# ESP32.net
KiCad netlist of a schematic drawn in Altium Designer
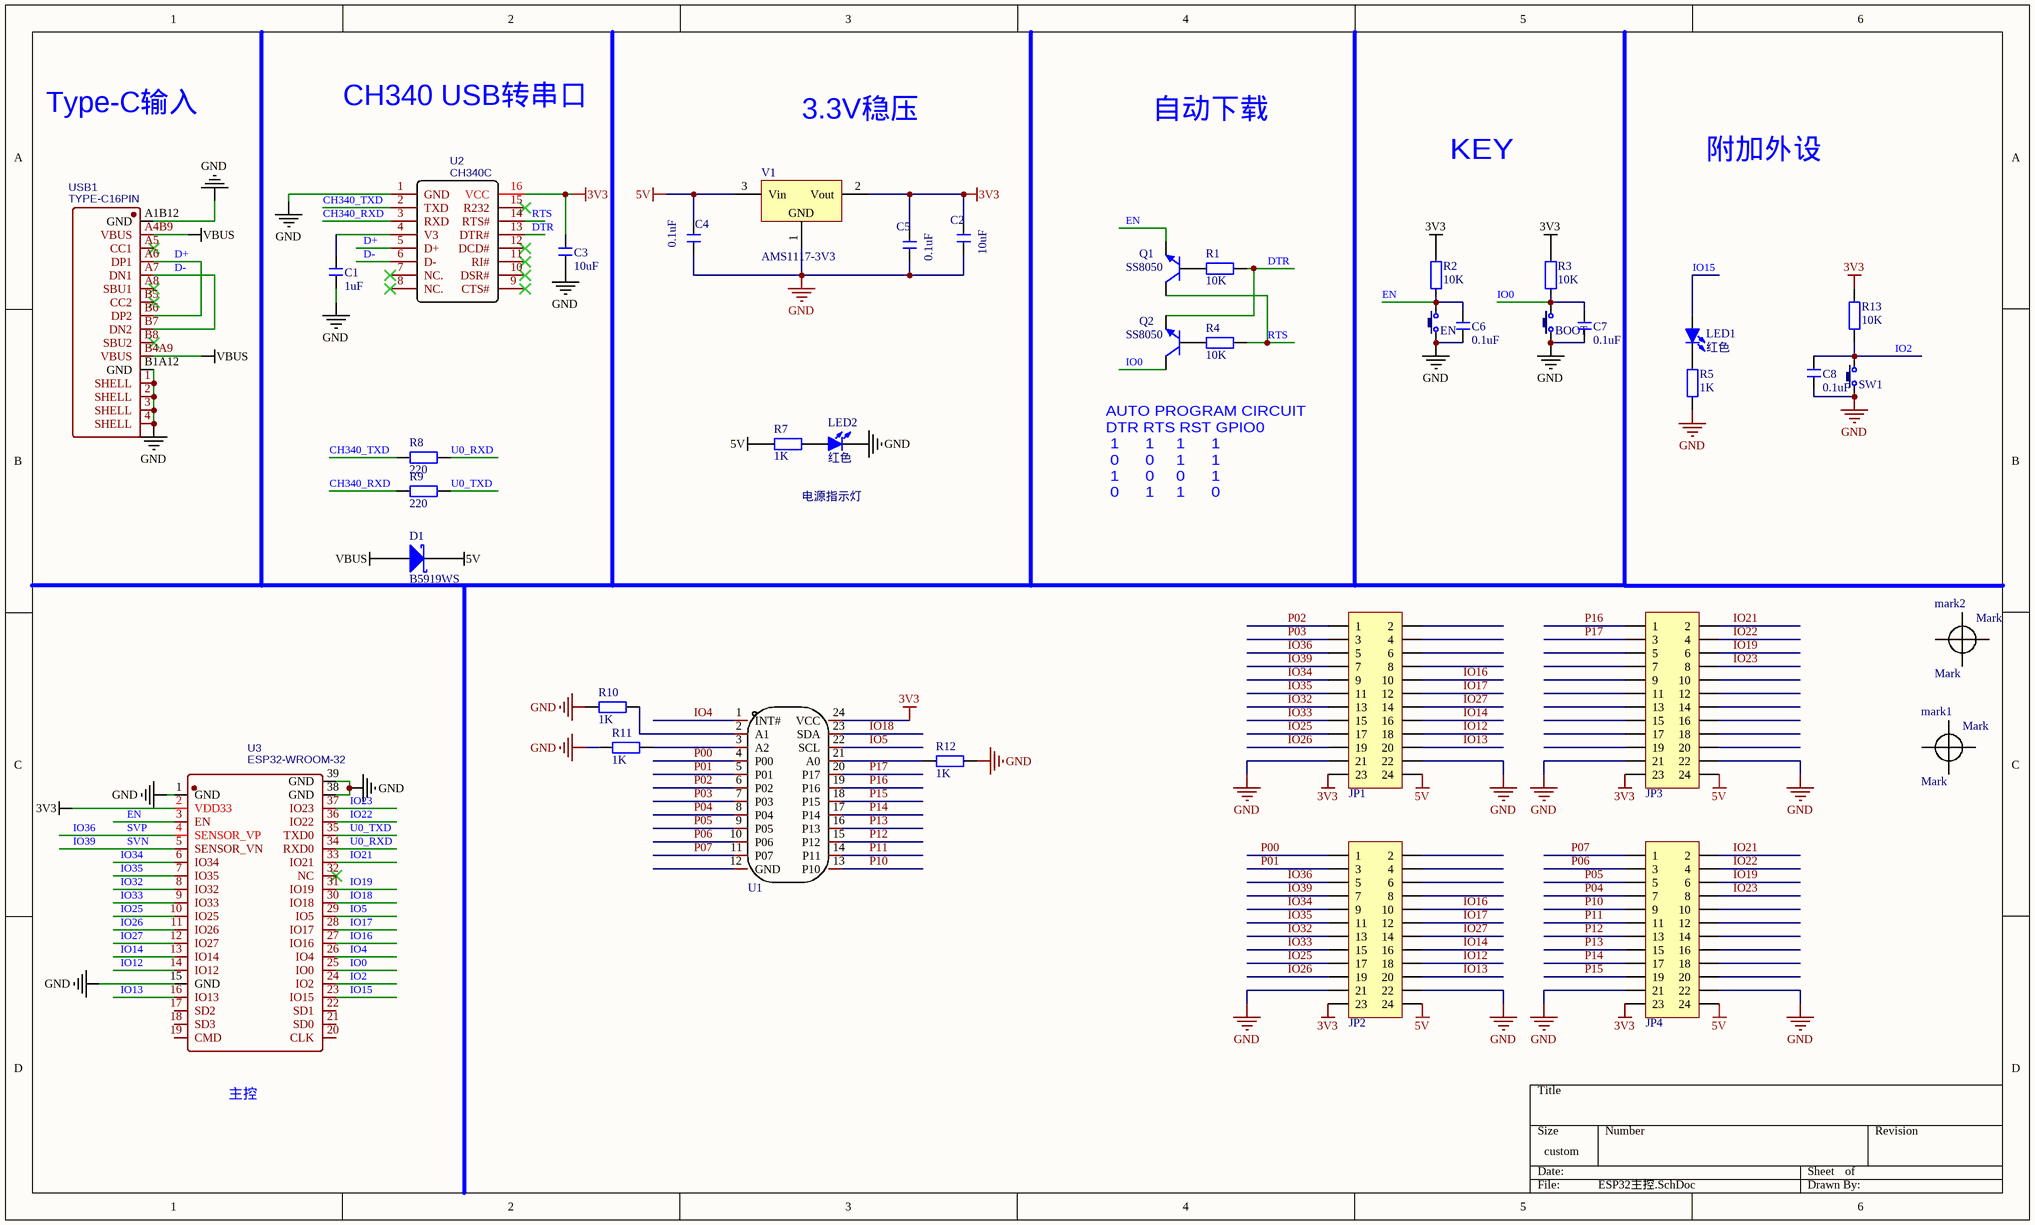
[diagram p0: ESP32主控.SchDoc]

(export (version "E")
  (design (tool "Eeschema 10.0.6"))
  (components
    (comp (ref "BOOT")
      (value "3x6x5")
      (footprint "TSW SMD-3*6*2.5")
      (description "3x6轻触开关")
      (fields (field (name "版权归属") "封装库来自淘宝 ID：黄晶宝石"))
      (libsource (lib "0.7 - 常用按键-开关") (part "TSW 3x6"))
    )
    (comp (ref "C1")
      (value "1uF")
      (footprint "C 0603_L")
      (description "贴片电容")
      (libsource (lib "0.1 - 电阻-电容-电感") (part "C"))
    )
    (comp (ref "C2")
      (value "10uF")
      (footprint "C 0603_M")
      (description "贴片电容")
      (libsource (lib "0.1 - 电阻-电容-电感") (part "C"))
    )
    (comp (ref "C3")
      (value "10uF")
      (footprint "C 0603_L")
      (description "贴片电容")
      (libsource (lib "0.1 - 电阻-电容-电感") (part "C"))
    )
    (comp (ref "C4")
      (value "0.1uF")
      (footprint "C 0603_M")
      (description "贴片电容")
      (libsource (lib "0.1 - 电阻-电容-电感") (part "C"))
    )
    (comp (ref "C5")
      (value "0.1uF")
      (footprint "C 0603_M")
      (description "贴片电容")
      (libsource (lib "0.1 - 电阻-电容-电感") (part "C"))
    )
    (comp (ref "C6")
      (value "0.1uF")
      (footprint "C 0603_L")
      (description "贴片电容")
      (libsource (lib "0.1 - 电阻-电容-电感") (part "C"))
    )
    (comp (ref "C7")
      (value "0.1uF")
      (footprint "C 0603_L")
      (description "贴片电容")
      (libsource (lib "0.1 - 电阻-电容-电感") (part "C"))
    )
    (comp (ref "C8")
      (value "0.1uF")
      (footprint "C 0603_L")
      (description "贴片电容")
      (libsource (lib "0.1 - 电阻-电容-电感") (part "C"))
    )
    (comp (ref "D1")
      (value "B5919WS")
      (footprint "SOD-323")
      (description "肖特基二极管")
      (libsource (lib "0.2 - 二极管-整流桥") (part "1N5819"))
    )
    (comp (ref "EN")
      (value "3x6x5")
      (footprint "TSW SMD-3*6*2.5")
      (description "3x6轻触开关")
      (fields (field (name "版权归属") "封装库来自淘宝 ID：黄晶宝石"))
      (libsource (lib "0.7 - 常用按键-开关") (part "TSW 3x6"))
    )
    (comp (ref "JP1")
      (value "Header 2X11")
      (footprint "HDR2.54-WI-2x12P")
      (description "12*2P接插件")
      (fields (field (name "版权归属") "封装库来自淘宝卖家 ID：黄晶宝石"))
      (libsource (lib "5.4 - 接插件-脚距2.54 (100mil) ") (part "Header 12X2"))
    )
    (comp (ref "JP2")
      (value "Header 2X11")
      (footprint "HDR2.54-WI-2x12P")
      (description "12*2P接插件")
      (fields (field (name "版权归属") "封装库来自淘宝卖家 ID：黄晶宝石"))
      (libsource (lib "5.4 - 接插件-脚距2.54 (100mil) ") (part "Header 12X2"))
    )
    (comp (ref "JP3")
      (value "Header 2X11")
      (footprint "HDR2.54-WI-2x12P")
      (description "12*2P接插件")
      (fields (field (name "版权归属") "封装库来自淘宝卖家 ID：黄晶宝石"))
      (libsource (lib "5.4 - 接插件-脚距2.54 (100mil) ") (part "Header 12X2"))
    )
    (comp (ref "JP4")
      (value "Header 2X11")
      (footprint "HDR2.54-WI-2x12P")
      (description "12*2P接插件")
      (fields (field (name "版权归属") "封装库来自淘宝卖家 ID：黄晶宝石"))
      (libsource (lib "5.4 - 接插件-脚距2.54 (100mil) ") (part "Header 12X2"))
    )
    (comp (ref "LED1")
      (value "红色")
      (footprint "LED 0603R")
      (description "贴片LED")
      (fields (field (name "版权归属") "封装库来自淘宝 ID：黄晶宝石"))
      (libsource (lib "0.3 - LED发光二极管") (part "LED-SMD"))
    )
    (comp (ref "LED2")
      (value "红色")
      (footprint "LED 0603R")
      (description "贴片LED")
      (fields (field (name "版权归属") "封装库来自淘宝 ID：黄晶宝石"))
      (libsource (lib "0.3 - LED发光二极管") (part "LED-SMD"))
    )
    (comp (ref "mark1") (value "Mark") (footprint "Mark:Mark") (libsource (lib "Mark") (part "Mark")))
    (comp (ref "mark2") (value "Mark") (footprint "Mark:Mark") (libsource (lib "Mark") (part "Mark")))
    (comp (ref "Q1")
      (value "SS8050")
      (footprint "SOT23-3N")
      (description "高频放大-NPN型")
      (fields (field (name "版权归属") "封装库来自淘宝 ID：黄晶宝石"))
      (libsource (lib "0.4 - 三极管") (part "8050-SMD"))
    )
    (comp (ref "Q2")
      (value "SS8050")
      (footprint "SOT23-3N")
      (description "高频放大-NPN型")
      (fields (field (name "版权归属") "封装库来自淘宝 ID：黄晶宝石"))
      (libsource (lib "0.4 - 三极管") (part "8050-SMD"))
    )
    (comp (ref "R1")
      (value "10K")
      (footprint "R 0603_L")
      (description "贴片电阻")
      (fields (field (name "版权归属") "来自淘宝 ID：黄晶宝石"))
      (libsource (lib "0.1 - 电阻-电容-电感") (part "R"))
    )
    (comp (ref "R2")
      (value "10K")
      (footprint "R 0603_L")
      (description "贴片电阻")
      (fields (field (name "版权归属") "来自淘宝 ID：黄晶宝石"))
      (libsource (lib "0.1 - 电阻-电容-电感") (part "R"))
    )
    (comp (ref "R3")
      (value "10K")
      (footprint "R 0603_L")
      (description "贴片电阻")
      (fields (field (name "版权归属") "来自淘宝 ID：黄晶宝石"))
      (libsource (lib "0.1 - 电阻-电容-电感") (part "R"))
    )
    (comp (ref "R4")
      (value "10K")
      (footprint "R 0603_L")
      (description "贴片电阻")
      (fields (field (name "版权归属") "来自淘宝 ID：黄晶宝石"))
      (libsource (lib "0.1 - 电阻-电容-电感") (part "R"))
    )
    (comp (ref "R5")
      (value "1K")
      (footprint "R 0603_L")
      (description "贴片电阻")
      (fields (field (name "版权归属") "来自淘宝 ID：黄晶宝石"))
      (libsource (lib "0.1 - 电阻-电容-电感") (part "R"))
    )
    (comp (ref "R7")
      (value "1K")
      (footprint "R 0603_L")
      (description "贴片电阻")
      (fields (field (name "版权归属") "来自淘宝 ID：黄晶宝石"))
      (libsource (lib "0.1 - 电阻-电容-电感") (part "R"))
    )
    (comp (ref "R8")
      (value "220")
      (footprint "R 0603_L")
      (description "贴片电阻")
      (fields (field (name "版权归属") "来自淘宝 ID：黄晶宝石"))
      (libsource (lib "0.1 - 电阻-电容-电感") (part "R"))
    )
    (comp (ref "R9")
      (value "220")
      (footprint "R 0603_L")
      (description "贴片电阻")
      (fields (field (name "版权归属") "来自淘宝 ID：黄晶宝石"))
      (libsource (lib "0.1 - 电阻-电容-电感") (part "R"))
    )
    (comp (ref "R10")
      (value "1K")
      (footprint "R 0603_L")
      (description "贴片电阻")
      (fields (field (name "版权归属") "来自淘宝 ID：黄晶宝石"))
      (libsource (lib "0.1 - 电阻-电容-电感") (part "R"))
    )
    (comp (ref "R11")
      (value "1K")
      (footprint "R 0603_L")
      (description "贴片电阻")
      (fields (field (name "版权归属") "来自淘宝 ID：黄晶宝石"))
      (libsource (lib "0.1 - 电阻-电容-电感") (part "R"))
    )
    (comp (ref "R12")
      (value "1K")
      (footprint "R 0603_L")
      (description "贴片电阻")
      (fields (field (name "版权归属") "来自淘宝 ID：黄晶宝石"))
      (libsource (lib "0.1 - 电阻-电容-电感") (part "R"))
    )
    (comp (ref "R13")
      (value "10K")
      (footprint "R 0603_L")
      (description "贴片电阻")
      (fields (field (name "版权归属") "来自淘宝 ID：黄晶宝石"))
      (libsource (lib "0.1 - 电阻-电容-电感") (part "R"))
    )
    (comp (ref "SW1")
      (value "3x6x5")
      (footprint "TSW SMD-3*6*2.5")
      (description "3x6轻触开关")
      (fields (field (name "版权归属") "封装库来自淘宝 ID：黄晶宝石"))
      (libsource (lib "0.7 - 常用按键-开关") (part "TSW 3x6"))
    )
    (comp (ref "U1")
      (value "PCA9555DW")
      (footprint "PCA9555DW")
      (description "具有中断、弱上拉和配置寄存器的 16 位 2.3V 至 5.5V I2C/SMBus I/O 扩展器 24-SOIC -40 to 85")
      (fields (field (name "MANUFACTURER") "TI(德州仪器)"))
      (libsource (lib "PCA9555DW") (part "PCA9555DW"))
    )
    (comp (ref "U2")
      (value "CH340C")
      (footprint "SOP-16_L10.0-W3.9-P1.27-LS6.0-BL")
      (fields (field (name "BOM_SUPPLIER PART") "C84681"))
      (libsource (lib "altium-import") (part "root_0_CH340C_"))
    )
    (comp (ref "U3")
      (value "ESP32-WROOM-32")
      (footprint "WIFIM-SMD_39P-L25.5-W18.0-P1.27")
      (fields (field (name "BOM_SUPPLIER PART") "C503587") (field (name "CONTRIBUTOR") "LCSC"))
      (libsource (lib "altium-import") (part "root_0_ESP32-WROOM-32_"))
    )
    (comp (ref "USB1")
      (value "TYPE-C16PIN")
      (footprint "USB-C-SMD_TYPE-C16PIN")
      (fields (field (name "BOM_SUPPLIER PART") "C393939") (field (name "CONTRIBUTOR") "LCSC"))
      (libsource (lib "altium-import") (part "root_0_TYPE-C16PIN_"))
    )
    (comp (ref "V1")
      (value "AMS1117-3V3")
      (footprint "SOT223_L")
      (description "三端稳压芯片")
      (libsource (lib "1.1 - 电源类芯片") (part "AMS1117"))
    )
  )
  (nets
    (net (code "1") (name "/CH340_RXD") (class "Default")
      (node (ref "R9") (pin "1") (pinfunction "1_1") (pintype "passive"))
      (node (ref "U2") (pin "3") (pinfunction "RXD_3") (pintype "passive"))
    )
    (net (code "2") (name "/CH340_TXD") (class "Default")
      (node (ref "R8") (pin "1") (pinfunction "1_1") (pintype "passive"))
      (node (ref "U2") (pin "2") (pinfunction "TXD_2") (pintype "passive"))
    )
    (net (code "3") (name "/D+") (class "Default")
      (node (ref "U2") (pin "5") (pinfunction "D+_5") (pintype "passive"))
      (node (ref "USB1") (pin "A6") (pinfunction "DP1_A6") (pintype "passive"))
      (node (ref "USB1") (pin "B6") (pinfunction "DP2_B6") (pintype "passive"))
    )
    (net (code "4") (name "/D-") (class "Default")
      (node (ref "U2") (pin "6") (pinfunction "D-_6") (pintype "passive"))
      (node (ref "USB1") (pin "A7") (pinfunction "DN1_A7") (pintype "passive"))
      (node (ref "USB1") (pin "B7") (pinfunction "DN2_B7") (pintype "passive"))
    )
    (net (code "5") (name "/DTR") (class "Default")
      (node (ref "Q2") (pin "2") (pinfunction "E_2") (pintype "passive"))
      (node (ref "R1") (pin "2") (pinfunction "2_2") (pintype "passive"))
      (node (ref "U2") (pin "13") (pinfunction "DTR#_13") (pintype "passive"))
    )
    (net (code "6") (name "/EN") (class "Default")
      (node (ref "C6") (pin "2") (pinfunction "2_2") (pintype "passive"))
      (node (ref "EN") (pin "2") (pinfunction "2_2") (pintype "passive"))
      (node (ref "Q1") (pin "2") (pinfunction "E_2") (pintype "passive"))
      (node (ref "R2") (pin "1") (pinfunction "1_1") (pintype "passive"))
      (node (ref "U3") (pin "3") (pinfunction "EN_3") (pintype "passive"))
    )
    (net (code "7") (name "/IO0") (class "Default")
      (node (ref "BOOT") (pin "2") (pinfunction "2_2") (pintype "passive"))
      (node (ref "C7") (pin "2") (pinfunction "2_2") (pintype "passive"))
      (node (ref "Q2") (pin "3") (pinfunction "C_3") (pintype "passive"))
      (node (ref "R3") (pin "1") (pinfunction "1_1") (pintype "passive"))
      (node (ref "U3") (pin "25") (pinfunction "IO0_25") (pintype "passive"))
    )
    (net (code "8") (name "/IO2") (class "Default")
      (node (ref "C8") (pin "2") (pinfunction "2_2") (pintype "passive"))
      (node (ref "R13") (pin "1") (pinfunction "1_1") (pintype "passive"))
      (node (ref "SW1") (pin "2") (pinfunction "2_2") (pintype "passive"))
      (node (ref "U3") (pin "24") (pinfunction "IO2_24") (pintype "passive"))
    )
    (net (code "9") (name "/IO4") (class "Default")
      (node (ref "U1") (pin "1") (pinfunction "INT#_1") (pintype "passive"))
      (node (ref "U3") (pin "26") (pinfunction "IO4_26") (pintype "passive"))
    )
    (net (code "10") (name "/IO5") (class "Default")
      (node (ref "U1") (pin "22") (pinfunction "SCL_22") (pintype "passive"))
      (node (ref "U3") (pin "29") (pinfunction "IO5_29") (pintype "passive"))
    )
    (net (code "11") (name "/IO12") (class "Default")
      (node (ref "JP1") (pin "18") (pinfunction "18_18") (pintype "passive"))
      (node (ref "JP2") (pin "18") (pinfunction "18_18") (pintype "passive"))
      (node (ref "U3") (pin "14") (pinfunction "IO12_14") (pintype "passive"))
    )
    (net (code "12") (name "/IO13") (class "Default")
      (node (ref "JP1") (pin "20") (pinfunction "20_20") (pintype "passive"))
      (node (ref "JP2") (pin "20") (pinfunction "20_20") (pintype "passive"))
      (node (ref "U3") (pin "16") (pinfunction "IO13_16") (pintype "passive"))
    )
    (net (code "13") (name "/IO14") (class "Default")
      (node (ref "JP1") (pin "16") (pinfunction "16_16") (pintype "passive"))
      (node (ref "JP2") (pin "16") (pinfunction "16_16") (pintype "passive"))
      (node (ref "U3") (pin "13") (pinfunction "IO14_13") (pintype "passive"))
    )
    (net (code "14") (name "/IO15") (class "Default")
      (node (ref "LED1") (pin "1") (pinfunction "A_1") (pintype "passive"))
      (node (ref "U3") (pin "23") (pinfunction "IO15_23") (pintype "passive"))
    )
    (net (code "15") (name "/IO16") (class "Default")
      (node (ref "JP1") (pin "10") (pinfunction "10_10") (pintype "passive"))
      (node (ref "JP2") (pin "10") (pinfunction "10_10") (pintype "passive"))
      (node (ref "U3") (pin "27") (pinfunction "IO16_27") (pintype "passive"))
    )
    (net (code "16") (name "/IO17") (class "Default")
      (node (ref "JP1") (pin "12") (pinfunction "12_12") (pintype "passive"))
      (node (ref "JP2") (pin "12") (pinfunction "12_12") (pintype "passive"))
      (node (ref "U3") (pin "28") (pinfunction "IO17_28") (pintype "passive"))
    )
    (net (code "17") (name "/IO18") (class "Default")
      (node (ref "U1") (pin "23") (pinfunction "SDA_23") (pintype "passive"))
      (node (ref "U3") (pin "30") (pinfunction "IO18_30") (pintype "passive"))
    )
    (net (code "18") (name "/IO19") (class "Default")
      (node (ref "JP3") (pin "6") (pinfunction "6_6") (pintype "passive"))
      (node (ref "JP4") (pin "6") (pinfunction "6_6") (pintype "passive"))
      (node (ref "U3") (pin "31") (pinfunction "IO19_31") (pintype "passive"))
    )
    (net (code "19") (name "/IO21") (class "Default")
      (node (ref "JP3") (pin "2") (pinfunction "2_2") (pintype "passive"))
      (node (ref "JP4") (pin "2") (pinfunction "2_2") (pintype "passive"))
      (node (ref "U3") (pin "33") (pinfunction "IO21_33") (pintype "passive"))
    )
    (net (code "20") (name "/IO22") (class "Default")
      (node (ref "JP3") (pin "4") (pinfunction "4_4") (pintype "passive"))
      (node (ref "JP4") (pin "4") (pinfunction "4_4") (pintype "passive"))
      (node (ref "U3") (pin "36") (pinfunction "IO22_36") (pintype "passive"))
    )
    (net (code "21") (name "/IO23") (class "Default")
      (node (ref "JP3") (pin "8") (pinfunction "8_8") (pintype "passive"))
      (node (ref "JP4") (pin "8") (pinfunction "8_8") (pintype "passive"))
      (node (ref "U3") (pin "37") (pinfunction "IO23_37") (pintype "passive"))
    )
    (net (code "22") (name "/IO25") (class "Default")
      (node (ref "JP1") (pin "17") (pinfunction "17_17") (pintype "passive"))
      (node (ref "JP2") (pin "17") (pinfunction "17_17") (pintype "passive"))
      (node (ref "U3") (pin "10") (pinfunction "IO25_10") (pintype "passive"))
    )
    (net (code "23") (name "/IO26") (class "Default")
      (node (ref "JP1") (pin "19") (pinfunction "19_19") (pintype "passive"))
      (node (ref "JP2") (pin "19") (pinfunction "19_19") (pintype "passive"))
      (node (ref "U3") (pin "11") (pinfunction "IO26_11") (pintype "passive"))
    )
    (net (code "24") (name "/IO27") (class "Default")
      (node (ref "JP1") (pin "14") (pinfunction "14_14") (pintype "passive"))
      (node (ref "JP2") (pin "14") (pinfunction "14_14") (pintype "passive"))
      (node (ref "U3") (pin "12") (pinfunction "IO27_12") (pintype "passive"))
    )
    (net (code "25") (name "/IO32") (class "Default")
      (node (ref "JP1") (pin "13") (pinfunction "13_13") (pintype "passive"))
      (node (ref "JP2") (pin "13") (pinfunction "13_13") (pintype "passive"))
      (node (ref "U3") (pin "8") (pinfunction "IO32_8") (pintype "passive"))
    )
    (net (code "26") (name "/IO33") (class "Default")
      (node (ref "JP1") (pin "15") (pinfunction "15_15") (pintype "passive"))
      (node (ref "JP2") (pin "15") (pinfunction "15_15") (pintype "passive"))
      (node (ref "U3") (pin "9") (pinfunction "IO33_9") (pintype "passive"))
    )
    (net (code "27") (name "/IO34") (class "Default")
      (node (ref "JP1") (pin "9") (pinfunction "9_9") (pintype "passive"))
      (node (ref "JP2") (pin "9") (pinfunction "9_9") (pintype "passive"))
      (node (ref "U3") (pin "6") (pinfunction "IO34_6") (pintype "passive"))
    )
    (net (code "28") (name "/IO35") (class "Default")
      (node (ref "JP1") (pin "11") (pinfunction "11_11") (pintype "passive"))
      (node (ref "JP2") (pin "11") (pinfunction "11_11") (pintype "passive"))
      (node (ref "U3") (pin "7") (pinfunction "IO35_7") (pintype "passive"))
    )
    (net (code "29") (name "/IO36") (class "Default")
      (node (ref "JP1") (pin "5") (pinfunction "5_5") (pintype "passive"))
      (node (ref "JP2") (pin "5") (pinfunction "5_5") (pintype "passive"))
      (node (ref "U3") (pin "4") (pinfunction "SENSOR_VP_4") (pintype "passive"))
    )
    (net (code "30") (name "/IO39") (class "Default")
      (node (ref "JP1") (pin "7") (pinfunction "7_7") (pintype "passive"))
      (node (ref "JP2") (pin "7") (pinfunction "7_7") (pintype "passive"))
      (node (ref "U3") (pin "5") (pinfunction "SENSOR_VN_5") (pintype "passive"))
    )
    (net (code "31") (name "/P00") (class "Default")
      (node (ref "JP2") (pin "1") (pinfunction "1_1") (pintype "passive"))
      (node (ref "U1") (pin "4") (pinfunction "P00_4") (pintype "passive"))
    )
    (net (code "32") (name "/P01") (class "Default")
      (node (ref "JP2") (pin "3") (pinfunction "3_3") (pintype "passive"))
      (node (ref "U1") (pin "5") (pinfunction "P01_5") (pintype "passive"))
    )
    (net (code "33") (name "/P02") (class "Default")
      (node (ref "JP1") (pin "1") (pinfunction "1_1") (pintype "passive"))
      (node (ref "U1") (pin "6") (pinfunction "P02_6") (pintype "passive"))
    )
    (net (code "34") (name "/P03") (class "Default")
      (node (ref "JP1") (pin "3") (pinfunction "3_3") (pintype "passive"))
      (node (ref "U1") (pin "7") (pinfunction "P03_7") (pintype "passive"))
    )
    (net (code "35") (name "/P04") (class "Default")
      (node (ref "JP4") (pin "7") (pinfunction "7_7") (pintype "passive"))
      (node (ref "U1") (pin "8") (pinfunction "P04_8") (pintype "passive"))
    )
    (net (code "36") (name "/P05") (class "Default")
      (node (ref "JP4") (pin "5") (pinfunction "5_5") (pintype "passive"))
      (node (ref "U1") (pin "9") (pinfunction "P05_9") (pintype "passive"))
    )
    (net (code "37") (name "/P06") (class "Default")
      (node (ref "JP4") (pin "3") (pinfunction "3_3") (pintype "passive"))
      (node (ref "U1") (pin "10") (pinfunction "P06_10") (pintype "passive"))
    )
    (net (code "38") (name "/P07") (class "Default")
      (node (ref "JP4") (pin "1") (pinfunction "1_1") (pintype "passive"))
      (node (ref "U1") (pin "11") (pinfunction "P07_11") (pintype "passive"))
    )
    (net (code "39") (name "/P10") (class "Default")
      (node (ref "JP4") (pin "9") (pinfunction "9_9") (pintype "passive"))
      (node (ref "U1") (pin "13") (pinfunction "P10_13") (pintype "passive"))
    )
    (net (code "40") (name "/P11") (class "Default")
      (node (ref "JP4") (pin "11") (pinfunction "11_11") (pintype "passive"))
      (node (ref "U1") (pin "14") (pinfunction "P11_14") (pintype "passive"))
    )
    (net (code "41") (name "/P12") (class "Default")
      (node (ref "JP4") (pin "13") (pinfunction "13_13") (pintype "passive"))
      (node (ref "U1") (pin "15") (pinfunction "P12_15") (pintype "passive"))
    )
    (net (code "42") (name "/P13") (class "Default")
      (node (ref "JP4") (pin "15") (pinfunction "15_15") (pintype "passive"))
      (node (ref "U1") (pin "16") (pinfunction "P13_16") (pintype "passive"))
    )
    (net (code "43") (name "/P14") (class "Default")
      (node (ref "JP4") (pin "17") (pinfunction "17_17") (pintype "passive"))
      (node (ref "U1") (pin "17") (pinfunction "P14_17") (pintype "passive"))
    )
    (net (code "44") (name "/P15") (class "Default")
      (node (ref "JP4") (pin "19") (pinfunction "19_19") (pintype "passive"))
      (node (ref "U1") (pin "18") (pinfunction "P15_18") (pintype "passive"))
    )
    (net (code "45") (name "/P16") (class "Default")
      (node (ref "JP3") (pin "1") (pinfunction "1_1") (pintype "passive"))
      (node (ref "U1") (pin "19") (pinfunction "P16_19") (pintype "passive"))
    )
    (net (code "46") (name "/P17") (class "Default")
      (node (ref "JP3") (pin "3") (pinfunction "3_3") (pintype "passive"))
      (node (ref "U1") (pin "20") (pinfunction "P17_20") (pintype "passive"))
    )
    (net (code "47") (name "/RTS") (class "Default")
      (node (ref "Q1") (pin "3") (pinfunction "C_3") (pintype "passive"))
      (node (ref "R4") (pin "2") (pinfunction "2_2") (pintype "passive"))
      (node (ref "U2") (pin "14") (pinfunction "RTS#_14") (pintype "passive"))
    )
    (net (code "48") (name "/U0_RXD") (class "Default")
      (node (ref "R8") (pin "2") (pinfunction "2_2") (pintype "passive"))
      (node (ref "U3") (pin "34") (pinfunction "RXD0_34") (pintype "passive"))
    )
    (net (code "49") (name "/U0_TXD") (class "Default")
      (node (ref "R9") (pin "2") (pinfunction "2_2") (pintype "passive"))
      (node (ref "U3") (pin "35") (pinfunction "TXD0_35") (pintype "passive"))
    )
    (net (code "50") (name "3V3") (class "Default")
      (node (ref "C2") (pin "2") (pinfunction "2_2") (pintype "passive"))
      (node (ref "C3") (pin "2") (pinfunction "2_2") (pintype "passive"))
      (node (ref "C5") (pin "2") (pinfunction "2_2") (pintype "passive"))
      (node (ref "JP1") (pin "23") (pinfunction "23_23") (pintype "passive"))
      (node (ref "JP2") (pin "23") (pinfunction "23_23") (pintype "passive"))
      (node (ref "JP3") (pin "23") (pinfunction "23_23") (pintype "passive"))
      (node (ref "JP4") (pin "23") (pinfunction "23_23") (pintype "passive"))
      (node (ref "R13") (pin "2") (pinfunction "2_2") (pintype "passive"))
      (node (ref "R2") (pin "2") (pinfunction "2_2") (pintype "passive"))
      (node (ref "R3") (pin "2") (pinfunction "2_2") (pintype "passive"))
      (node (ref "U1") (pin "24") (pinfunction "VCC_24") (pintype "passive"))
      (node (ref "U2") (pin "16") (pinfunction "VCC_16") (pintype "passive"))
      (node (ref "U3") (pin "2") (pinfunction "VDD33_2") (pintype "passive"))
      (node (ref "V1") (pin "2") (pinfunction "Vout_2") (pintype "passive"))
    )
    (net (code "51") (name "5V") (class "Default")
      (node (ref "C4") (pin "2") (pinfunction "2_2") (pintype "passive"))
      (node (ref "D1") (pin "2") (pinfunction "K_2") (pintype "passive"))
      (node (ref "JP1") (pin "24") (pinfunction "24_24") (pintype "passive"))
      (node (ref "JP2") (pin "24") (pinfunction "24_24") (pintype "passive"))
      (node (ref "JP3") (pin "24") (pinfunction "24_24") (pintype "passive"))
      (node (ref "JP4") (pin "24") (pinfunction "24_24") (pintype "passive"))
      (node (ref "R7") (pin "1") (pinfunction "1_1") (pintype "passive"))
      (node (ref "V1") (pin "3") (pinfunction "Vin_3") (pintype "passive"))
    )
    (net (code "52") (name "GND") (class "Default")
      (node (ref "BOOT") (pin "1") (pinfunction "1_1") (pintype "passive"))
      (node (ref "C1") (pin "1") (pinfunction "1_1") (pintype "passive"))
      (node (ref "C2") (pin "1") (pinfunction "1_1") (pintype "passive"))
      (node (ref "C3") (pin "1") (pinfunction "1_1") (pintype "passive"))
      (node (ref "C4") (pin "1") (pinfunction "1_1") (pintype "passive"))
      (node (ref "C5") (pin "1") (pinfunction "1_1") (pintype "passive"))
      (node (ref "C6") (pin "1") (pinfunction "1_1") (pintype "passive"))
      (node (ref "C7") (pin "1") (pinfunction "1_1") (pintype "passive"))
      (node (ref "C8") (pin "1") (pinfunction "1_1") (pintype "passive"))
      (node (ref "EN") (pin "1") (pinfunction "1_1") (pintype "passive"))
      (node (ref "JP1") (pin "21") (pinfunction "21_21") (pintype "passive"))
      (node (ref "JP1") (pin "22") (pinfunction "22_22") (pintype "passive"))
      (node (ref "JP2") (pin "21") (pinfunction "21_21") (pintype "passive"))
      (node (ref "JP2") (pin "22") (pinfunction "22_22") (pintype "passive"))
      (node (ref "JP3") (pin "21") (pinfunction "21_21") (pintype "passive"))
      (node (ref "JP3") (pin "22") (pinfunction "22_22") (pintype "passive"))
      (node (ref "JP4") (pin "21") (pinfunction "21_21") (pintype "passive"))
      (node (ref "JP4") (pin "22") (pinfunction "22_22") (pintype "passive"))
      (node (ref "LED2") (pin "2") (pinfunction "K_2") (pintype "passive"))
      (node (ref "R10") (pin "1") (pinfunction "1_1") (pintype "passive"))
      (node (ref "R11") (pin "1") (pinfunction "1_1") (pintype "passive"))
      (node (ref "R12") (pin "2") (pinfunction "2_2") (pintype "passive"))
      (node (ref "R5") (pin "1") (pinfunction "1_1") (pintype "passive"))
      (node (ref "SW1") (pin "1") (pinfunction "1_1") (pintype "passive"))
      (node (ref "U2") (pin "1") (pinfunction "GND_1") (pintype "passive"))
      (node (ref "U3") (pin "1") (pinfunction "GND_1") (pintype "passive"))
      (node (ref "U3") (pin "15") (pinfunction "GND_15") (pintype "passive"))
      (node (ref "U3") (pin "38") (pinfunction "GND_38") (pintype "passive"))
      (node (ref "U3") (pin "39") (pinfunction "GND_39") (pintype "passive"))
      (node (ref "USB1") (pin "1") (pinfunction "SHELL_1") (pintype "passive"))
      (node (ref "USB1") (pin "2") (pinfunction "SHELL_2") (pintype "passive"))
      (node (ref "USB1") (pin "3") (pinfunction "SHELL_3") (pintype "passive"))
      (node (ref "USB1") (pin "4") (pinfunction "SHELL_4") (pintype "passive"))
      (node (ref "USB1") (pin "A1B12") (pinfunction "GND_A1B12") (pintype "passive"))
      (node (ref "USB1") (pin "B1A12") (pinfunction "GND_B1A12") (pintype "passive"))
      (node (ref "V1") (pin "1") (pinfunction "GND_1") (pintype "passive"))
    )
    (net (code "53") (name "Net-(LED1-K)") (class "Default")
      (node (ref "LED1") (pin "2") (pinfunction "K_2") (pintype "passive"))
      (node (ref "R5") (pin "2") (pinfunction "2_2") (pintype "passive"))
    )
    (net (code "54") (name "Net-(LED2-A)") (class "Default")
      (node (ref "LED2") (pin "1") (pinfunction "A_1") (pintype "passive"))
      (node (ref "R7") (pin "2") (pinfunction "2_2") (pintype "passive"))
    )
    (net (code "55") (name "Net-(Q1-B)") (class "Default")
      (node (ref "Q1") (pin "1") (pinfunction "B_1") (pintype "passive"))
      (node (ref "R1") (pin "1") (pinfunction "1_1") (pintype "passive"))
    )
    (net (code "56") (name "Net-(Q2-B)") (class "Default")
      (node (ref "Q2") (pin "1") (pinfunction "B_1") (pintype "passive"))
      (node (ref "R4") (pin "1") (pinfunction "1_1") (pintype "passive"))
    )
    (net (code "57") (name "Net-(U1-A0)") (class "Default")
      (node (ref "R12") (pin "1") (pinfunction "1_1") (pintype "passive"))
      (node (ref "U1") (pin "21") (pinfunction "A0_21") (pintype "passive"))
    )
    (net (code "58") (name "Net-(U1-A1)") (class "Default")
      (node (ref "R10") (pin "2") (pinfunction "2_2") (pintype "passive"))
      (node (ref "U1") (pin "2") (pinfunction "A1_2") (pintype "passive"))
    )
    (net (code "59") (name "Net-(U1-A2)") (class "Default")
      (node (ref "R11") (pin "2") (pinfunction "2_2") (pintype "passive"))
      (node (ref "U1") (pin "3") (pinfunction "A2_3") (pintype "passive"))
    )
    (net (code "60") (name "Net-(U2-V3)") (class "Default")
      (node (ref "C1") (pin "2") (pinfunction "2_2") (pintype "passive"))
      (node (ref "U2") (pin "4") (pinfunction "V3_4") (pintype "passive"))
    )
    (net (code "61") (name "VBUS") (class "Default")
      (node (ref "D1") (pin "1") (pinfunction "A_1") (pintype "passive"))
      (node (ref "USB1") (pin "A4B9") (pinfunction "VBUS_A4B9") (pintype "passive"))
      (node (ref "USB1") (pin "B4A9") (pinfunction "VBUS_B4A9") (pintype "passive"))
    )
    (net (code "62") (name "unconnected-(JP1-Pad2)") (class "Default")
      (node (ref "JP1") (pin "2") (pinfunction "2_2") (pintype "passive"))
    )
    (net (code "63") (name "unconnected-(JP1-Pad4)") (class "Default")
      (node (ref "JP1") (pin "4") (pinfunction "4_4") (pintype "passive"))
    )
    (net (code "64") (name "unconnected-(JP1-Pad6)") (class "Default")
      (node (ref "JP1") (pin "6") (pinfunction "6_6") (pintype "passive"))
    )
    (net (code "65") (name "unconnected-(JP1-Pad8)") (class "Default")
      (node (ref "JP1") (pin "8") (pinfunction "8_8") (pintype "passive"))
    )
    (net (code "66") (name "unconnected-(JP2-Pad2)") (class "Default")
      (node (ref "JP2") (pin "2") (pinfunction "2_2") (pintype "passive"))
    )
    (net (code "67") (name "unconnected-(JP2-Pad4)") (class "Default")
      (node (ref "JP2") (pin "4") (pinfunction "4_4") (pintype "passive"))
    )
    (net (code "68") (name "unconnected-(JP2-Pad6)") (class "Default")
      (node (ref "JP2") (pin "6") (pinfunction "6_6") (pintype "passive"))
    )
    (net (code "69") (name "unconnected-(JP2-Pad8)") (class "Default")
      (node (ref "JP2") (pin "8") (pinfunction "8_8") (pintype "passive"))
    )
    (net (code "70") (name "unconnected-(JP3-Pad5)") (class "Default")
      (node (ref "JP3") (pin "5") (pinfunction "5_5") (pintype "passive"))
    )
    (net (code "71") (name "unconnected-(JP3-Pad7)") (class "Default")
      (node (ref "JP3") (pin "7") (pinfunction "7_7") (pintype "passive"))
    )
    (net (code "72") (name "unconnected-(JP3-Pad9)") (class "Default")
      (node (ref "JP3") (pin "9") (pinfunction "9_9") (pintype "passive"))
    )
    (net (code "73") (name "unconnected-(JP3-Pad10)") (class "Default")
      (node (ref "JP3") (pin "10") (pinfunction "10_10") (pintype "passive"))
    )
    (net (code "74") (name "unconnected-(JP3-Pad11)") (class "Default")
      (node (ref "JP3") (pin "11") (pinfunction "11_11") (pintype "passive"))
    )
    (net (code "75") (name "unconnected-(JP3-Pad12)") (class "Default")
      (node (ref "JP3") (pin "12") (pinfunction "12_12") (pintype "passive"))
    )
    (net (code "76") (name "unconnected-(JP3-Pad13)") (class "Default")
      (node (ref "JP3") (pin "13") (pinfunction "13_13") (pintype "passive"))
    )
    (net (code "77") (name "unconnected-(JP3-Pad14)") (class "Default")
      (node (ref "JP3") (pin "14") (pinfunction "14_14") (pintype "passive"))
    )
    (net (code "78") (name "unconnected-(JP3-Pad15)") (class "Default")
      (node (ref "JP3") (pin "15") (pinfunction "15_15") (pintype "passive"))
    )
    (net (code "79") (name "unconnected-(JP3-Pad16)") (class "Default")
      (node (ref "JP3") (pin "16") (pinfunction "16_16") (pintype "passive"))
    )
    (net (code "80") (name "unconnected-(JP3-Pad17)") (class "Default")
      (node (ref "JP3") (pin "17") (pinfunction "17_17") (pintype "passive"))
    )
    (net (code "81") (name "unconnected-(JP3-Pad18)") (class "Default")
      (node (ref "JP3") (pin "18") (pinfunction "18_18") (pintype "passive"))
    )
    (net (code "82") (name "unconnected-(JP3-Pad19)") (class "Default")
      (node (ref "JP3") (pin "19") (pinfunction "19_19") (pintype "passive"))
    )
    (net (code "83") (name "unconnected-(JP3-Pad20)") (class "Default")
      (node (ref "JP3") (pin "20") (pinfunction "20_20") (pintype "passive"))
    )
    (net (code "84") (name "unconnected-(JP4-Pad10)") (class "Default")
      (node (ref "JP4") (pin "10") (pinfunction "10_10") (pintype "passive"))
    )
    (net (code "85") (name "unconnected-(JP4-Pad12)") (class "Default")
      (node (ref "JP4") (pin "12") (pinfunction "12_12") (pintype "passive"))
    )
    (net (code "86") (name "unconnected-(JP4-Pad14)") (class "Default")
      (node (ref "JP4") (pin "14") (pinfunction "14_14") (pintype "passive"))
    )
    (net (code "87") (name "unconnected-(JP4-Pad16)") (class "Default")
      (node (ref "JP4") (pin "16") (pinfunction "16_16") (pintype "passive"))
    )
    (net (code "88") (name "unconnected-(JP4-Pad18)") (class "Default")
      (node (ref "JP4") (pin "18") (pinfunction "18_18") (pintype "passive"))
    )
    (net (code "89") (name "unconnected-(JP4-Pad20)") (class "Default")
      (node (ref "JP4") (pin "20") (pinfunction "20_20") (pintype "passive"))
    )
    (net (code "90") (name "unconnected-(U1-GND-Pad12)") (class "Default")
      (node (ref "U1") (pin "12") (pinfunction "GND_12") (pintype "passive"))
    )
    (net (code "91") (name "unconnected-(U2-CTS#-Pad9)") (class "Default")
      (node (ref "U2") (pin "9") (pinfunction "CTS#_9") (pintype "passive+no_connect"))
    )
    (net (code "92") (name "unconnected-(U2-DCD#-Pad12)") (class "Default")
      (node (ref "U2") (pin "12") (pinfunction "DCD#_12") (pintype "passive+no_connect"))
    )
    (net (code "93") (name "unconnected-(U2-DSR#-Pad10)") (class "Default")
      (node (ref "U2") (pin "10") (pinfunction "DSR#_10") (pintype "passive+no_connect"))
    )
    (net (code "94") (name "unconnected-(U2-NC.-Pad7)") (class "Default")
      (node (ref "U2") (pin "7") (pinfunction "NC._7") (pintype "passive+no_connect"))
    )
    (net (code "95") (name "unconnected-(U2-NC.-Pad8)") (class "Default")
      (node (ref "U2") (pin "8") (pinfunction "NC._8") (pintype "passive+no_connect"))
    )
    (net (code "96") (name "unconnected-(U2-R232-Pad15)") (class "Default")
      (node (ref "U2") (pin "15") (pinfunction "R232_15") (pintype "passive+no_connect"))
    )
    (net (code "97") (name "unconnected-(U2-RI#-Pad11)") (class "Default")
      (node (ref "U2") (pin "11") (pinfunction "RI#_11") (pintype "passive+no_connect"))
    )
    (net (code "98") (name "unconnected-(U3-CLK-Pad20)") (class "Default")
      (node (ref "U3") (pin "20") (pinfunction "CLK_20") (pintype "passive"))
    )
    (net (code "99") (name "unconnected-(U3-CMD-Pad19)") (class "Default")
      (node (ref "U3") (pin "19") (pinfunction "CMD_19") (pintype "passive"))
    )
    (net (code "100") (name "unconnected-(U3-NC-Pad32)") (class "Default")
      (node (ref "U3") (pin "32") (pinfunction "NC_32") (pintype "passive+no_connect"))
    )
    (net (code "101") (name "unconnected-(U3-SD0-Pad21)") (class "Default")
      (node (ref "U3") (pin "21") (pinfunction "SD0_21") (pintype "passive"))
    )
    (net (code "102") (name "unconnected-(U3-SD1-Pad22)") (class "Default")
      (node (ref "U3") (pin "22") (pinfunction "SD1_22") (pintype "passive"))
    )
    (net (code "103") (name "unconnected-(U3-SD2-Pad17)") (class "Default")
      (node (ref "U3") (pin "17") (pinfunction "SD2_17") (pintype "passive"))
    )
    (net (code "104") (name "unconnected-(U3-SD3-Pad18)") (class "Default")
      (node (ref "U3") (pin "18") (pinfunction "SD3_18") (pintype "passive"))
    )
    (net (code "105") (name "unconnected-(USB1-CC1-PadA5)") (class "Default")
      (node (ref "USB1") (pin "A5") (pinfunction "CC1_A5") (pintype "passive+no_connect"))
    )
    (net (code "106") (name "unconnected-(USB1-CC2-PadB5)") (class "Default")
      (node (ref "USB1") (pin "B5") (pinfunction "CC2_B5") (pintype "passive+no_connect"))
    )
    (net (code "107") (name "unconnected-(USB1-SBU1-PadA8)") (class "Default")
      (node (ref "USB1") (pin "A8") (pinfunction "SBU1_A8") (pintype "passive+no_connect"))
    )
    (net (code "108") (name "unconnected-(USB1-SBU2-PadB8)") (class "Default")
      (node (ref "USB1") (pin "B8") (pinfunction "SBU2_B8") (pintype "passive+no_connect"))
    )
  )
)
